# MikerBotBottlenose.net
KiCad netlist of a schematic drawn in EAGLE
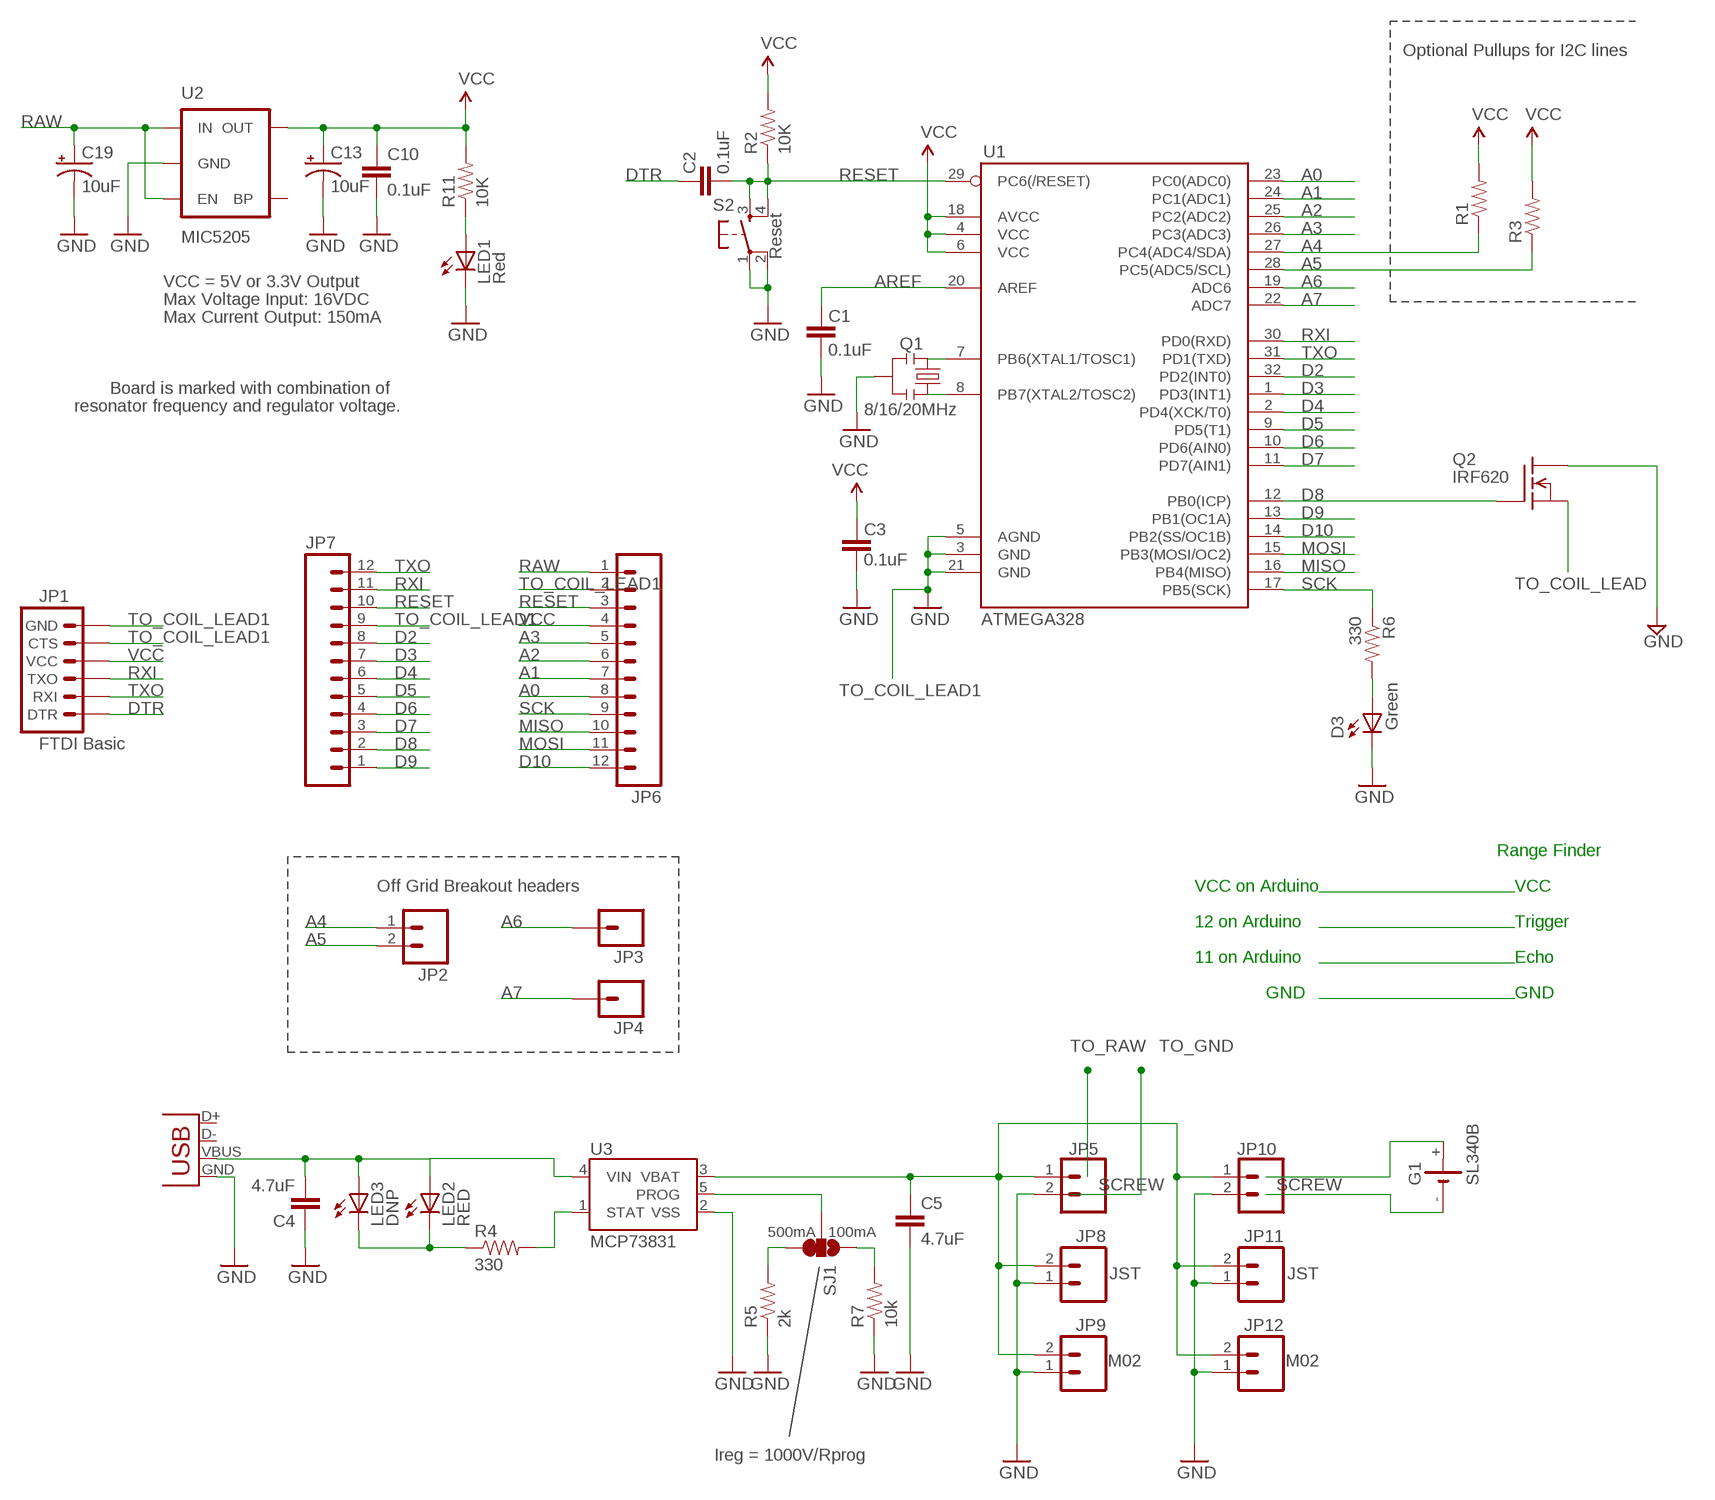
[diagram p0: schematic, sheet 1]

(export (version "E")
  (design (tool "Eeschema 10.0.6"))
  (components
    (comp (ref "C1")
      (value "0.1uF")
      (footprint "eagle-import:0402-CAP")
      (libsource (lib "eagle-import") (part "CAP0402-CAP"))
    )
    (comp (ref "C2")
      (value "0.1uF")
      (footprint "eagle-import:0402-CAP")
      (libsource (lib "eagle-import") (part "CAP0402-CAP"))
    )
    (comp (ref "C3")
      (value "0.1uF")
      (footprint "eagle-import:0402-CAP")
      (libsource (lib "eagle-import") (part "CAP0402-CAP"))
    )
    (comp (ref "C4")
      (value "4.7uF")
      (footprint "eagle-import:0402-CAP")
      (libsource (lib "eagle-import") (part "CAP0402-CAP"))
    )
    (comp (ref "C5")
      (value "4.7uF")
      (footprint "eagle-import:0402-CAP")
      (libsource (lib "eagle-import") (part "CAP0402-CAP"))
    )
    (comp (ref "C10")
      (value "0.1uF")
      (footprint "eagle-import:0402-CAP")
      (libsource (lib "eagle-import") (part "CAP0402-CAP"))
    )
    (comp (ref "C13")
      (value "10uF")
      (footprint "eagle-import:EIA3216")
      (libsource (lib "eagle-import") (part "CAP_POL1206"))
    )
    (comp (ref "C19")
      (value "10uF")
      (footprint "eagle-import:EIA3216")
      (libsource (lib "eagle-import") (part "CAP_POL1206"))
    )
    (comp (ref "D3")
      (value "Green")
      (footprint "eagle-import:LED-0603")
      (libsource (lib "eagle-import") (part "LED0603"))
    )
    (comp (ref "G1")
      (value "SL340B")
      (footprint "eagle-import:SL-340_B3.6V")
      (libsource (lib "eagle-import") (part "SL340B"))
    )
    (comp (ref "JP1")
      (value "FTDI Basic")
      (footprint "eagle-import:1X06")
      (libsource (lib "eagle-import") (part "ARDUINO_SERIAL_PROGRAMPTH"))
    )
    (comp (ref "JP2")
      (value "M02PTH")
      (footprint "eagle-import:1X02")
      (libsource (lib "eagle-import") (part "M02PTH"))
    )
    (comp (ref "JP3")
      (value "M01PTH")
      (footprint "eagle-import:1X01")
      (libsource (lib "eagle-import") (part "M01PTH"))
    )
    (comp (ref "JP4")
      (value "M01PTH")
      (footprint "eagle-import:1X01")
      (libsource (lib "eagle-import") (part "M01PTH"))
    )
    (comp (ref "JP5")
      (value "SCREW")
      (footprint "eagle-import:SCREWTERMINAL-3.5MM-2-NS")
      (libsource (lib "eagle-import") (part "M023.5MM-NO_SILK"))
    )
    (comp (ref "JP6")
      (value "M12PTH")
      (footprint "eagle-import:1X12")
      (libsource (lib "eagle-import") (part "M12PTH"))
    )
    (comp (ref "JP7")
      (value "M12PTH")
      (footprint "eagle-import:1X12")
      (libsource (lib "eagle-import") (part "M12PTH"))
    )
    (comp (ref "JP8")
      (value "JST")
      (footprint "eagle-import:JST-2-PTH")
      (libsource (lib "eagle-import") (part "M02JST-PTH-2"))
    )
    (comp (ref "JP9")
      (value "M02")
      (footprint "eagle-import:1X02")
      (libsource (lib "eagle-import") (part "M02PTH"))
    )
    (comp (ref "JP10")
      (value "SCREW")
      (footprint "eagle-import:SCREWTERMINAL-3.5MM-2-NS")
      (libsource (lib "eagle-import") (part "M023.5MM-NO_SILK"))
    )
    (comp (ref "JP11")
      (value "JST")
      (footprint "eagle-import:JST-2-PTH")
      (libsource (lib "eagle-import") (part "M02JST-PTH-2"))
    )
    (comp (ref "JP12")
      (value "M02")
      (footprint "eagle-import:1X02")
      (libsource (lib "eagle-import") (part "M02PTH"))
    )
    (comp (ref "LED1")
      (value "Red")
      (footprint "eagle-import:LED-0603")
      (libsource (lib "eagle-import") (part "LED0603"))
    )
    (comp (ref "LED2")
      (value "RED")
      (footprint "eagle-import:LED-0603")
      (libsource (lib "eagle-import") (part "LED0603"))
    )
    (comp (ref "LED3")
      (value "DNP")
      (footprint "eagle-import:LED3MM")
      (libsource (lib "eagle-import") (part "LED3MM"))
    )
    (comp (ref "Q1")
      (value "8/16/20MHz")
      (footprint "eagle-import:RESONATOR-SMD")
      (libsource (lib "eagle-import") (part "RESONATORSMD"))
    )
    (comp (ref "Q2")
      (value "IRF620")
      (footprint "eagle-import:TO220")
      (libsource (lib "eagle-import") (part "IRF620"))
    )
    (comp (ref "R1")
      (value "RESISTOR0402-RES")
      (footprint "eagle-import:0402-RES")
      (libsource (lib "eagle-import") (part "RESISTOR0402-RES"))
    )
    (comp (ref "R2")
      (value "10K")
      (footprint "eagle-import:0402-RES")
      (libsource (lib "eagle-import") (part "RESISTOR0402-RES"))
    )
    (comp (ref "R3")
      (value "RESISTOR0402-RES")
      (footprint "eagle-import:0402-RES")
      (libsource (lib "eagle-import") (part "RESISTOR0402-RES"))
    )
    (comp (ref "R4")
      (value "330")
      (footprint "eagle-import:0402-RES")
      (libsource (lib "eagle-import") (part "RESISTOR0402-RES"))
    )
    (comp (ref "R5")
      (value "2k")
      (footprint "eagle-import:0402-RES")
      (libsource (lib "eagle-import") (part "RESISTOR0402-RES"))
    )
    (comp (ref "R6")
      (value "330")
      (footprint "eagle-import:0402-RES")
      (libsource (lib "eagle-import") (part "RESISTOR0402-RES"))
    )
    (comp (ref "R7")
      (value "10k")
      (footprint "eagle-import:0402-RES")
      (libsource (lib "eagle-import") (part "RESISTOR0402-RES"))
    )
    (comp (ref "R11")
      (value "10K")
      (footprint "eagle-import:0402-RES")
      (libsource (lib "eagle-import") (part "RESISTOR0402-RES"))
    )
    (comp (ref "S2")
      (value "Reset")
      (footprint "eagle-import:TACTILE_SWITCH_SMD")
      (libsource (lib "eagle-import") (part "TAC_SWITCHSMD"))
    )
    (comp (ref "SJ1")
      (value "SOLDERJUMPER_2WAYS")
      (footprint "eagle-import:SJ_3")
      (libsource (lib "eagle-import") (part "SOLDERJUMPER_2WAYS"))
    )
    (comp (ref "U1")
      (value "ATMEGA328")
      (footprint "eagle-import:TQFP32-08")
      (libsource (lib "eagle-import") (part "ATMEGA168"))
    )
    (comp (ref "U2")
      (value "MIC5205")
      (footprint "eagle-import:SOT23-5")
      (libsource (lib "eagle-import") (part "V_REG_LDOSMD"))
    )
    (comp (ref "U3")
      (value "MCP73831")
      (footprint "eagle-import:SOT23-5")
      (libsource (lib "eagle-import") (part "MCP73831"))
    )
    (comp (ref "X1")
      (value "USBSMD")
      (footprint "eagle-import:USB-MINIB")
      (libsource (lib "eagle-import") (part "USBSMD"))
    )
  )
  (nets
    (net (code "1") (name "/A0") (class "Default")
      (node (ref "JP6") (pin "8") (pinfunction "8_8") (pintype "passive"))
      (node (ref "U1") (pin "23") (pinfunction "PC0(ADC0)_23") (pintype "bidirectional"))
    )
    (net (code "2") (name "/A1") (class "Default")
      (node (ref "JP6") (pin "7") (pinfunction "7_7") (pintype "passive"))
      (node (ref "U1") (pin "24") (pinfunction "PC1(ADC1)_24") (pintype "bidirectional"))
    )
    (net (code "3") (name "/A2") (class "Default")
      (node (ref "JP6") (pin "6") (pinfunction "6_6") (pintype "passive"))
      (node (ref "U1") (pin "25") (pinfunction "PC2(ADC2)_25") (pintype "bidirectional"))
    )
    (net (code "4") (name "/A3") (class "Default")
      (node (ref "JP6") (pin "5") (pinfunction "5_5") (pintype "passive"))
      (node (ref "U1") (pin "26") (pinfunction "PC3(ADC3)_26") (pintype "bidirectional"))
    )
    (net (code "5") (name "/A4") (class "Default")
      (node (ref "JP2") (pin "1") (pinfunction "1_1") (pintype "passive"))
      (node (ref "R1") (pin "1") (pinfunction "1_1") (pintype "passive"))
      (node (ref "U1") (pin "27") (pinfunction "PC4(ADC4/SDA)_27") (pintype "bidirectional"))
    )
    (net (code "6") (name "/A5") (class "Default")
      (node (ref "JP2") (pin "2") (pinfunction "2_2") (pintype "passive"))
      (node (ref "R3") (pin "1") (pinfunction "1_1") (pintype "passive"))
      (node (ref "U1") (pin "28") (pinfunction "PC5(ADC5/SCL)_28") (pintype "bidirectional"))
    )
    (net (code "7") (name "/A6") (class "Default")
      (node (ref "JP3") (pin "1") (pinfunction "1_1") (pintype "passive"))
      (node (ref "U1") (pin "19") (pinfunction "ADC6_19") (pintype "bidirectional"))
    )
    (net (code "8") (name "/A7") (class "Default")
      (node (ref "JP4") (pin "1") (pinfunction "1_1") (pintype "passive"))
      (node (ref "U1") (pin "22") (pinfunction "ADC7_22") (pintype "bidirectional"))
    )
    (net (code "9") (name "/AREF") (class "Default")
      (node (ref "C1") (pin "2") (pinfunction "2_2") (pintype "passive"))
      (node (ref "U1") (pin "20") (pinfunction "AREF_20") (pintype "bidirectional"))
    )
    (net (code "10") (name "/D2") (class "Default")
      (node (ref "JP7") (pin "8") (pinfunction "8_8") (pintype "passive"))
      (node (ref "U1") (pin "32") (pinfunction "PD2(INT0)_32") (pintype "bidirectional"))
    )
    (net (code "11") (name "/D3") (class "Default")
      (node (ref "JP7") (pin "7") (pinfunction "7_7") (pintype "passive"))
      (node (ref "U1") (pin "1") (pinfunction "PD3(INT1)_1") (pintype "bidirectional"))
    )
    (net (code "12") (name "/D4") (class "Default")
      (node (ref "JP7") (pin "6") (pinfunction "6_6") (pintype "passive"))
      (node (ref "U1") (pin "2") (pinfunction "PD4(XCK/T0)_2") (pintype "bidirectional"))
    )
    (net (code "13") (name "/D5") (class "Default")
      (node (ref "JP7") (pin "5") (pinfunction "5_5") (pintype "passive"))
      (node (ref "U1") (pin "9") (pinfunction "PD5(T1)_9") (pintype "bidirectional"))
    )
    (net (code "14") (name "/D6") (class "Default")
      (node (ref "JP7") (pin "4") (pinfunction "4_4") (pintype "passive"))
      (node (ref "U1") (pin "10") (pinfunction "PD6(AIN0)_10") (pintype "bidirectional"))
    )
    (net (code "15") (name "/D7") (class "Default")
      (node (ref "JP7") (pin "3") (pinfunction "3_3") (pintype "passive"))
      (node (ref "U1") (pin "11") (pinfunction "PD7(AIN1)_11") (pintype "bidirectional"))
    )
    (net (code "16") (name "/D8") (class "Default")
      (node (ref "JP7") (pin "2") (pinfunction "2_2") (pintype "passive"))
      (node (ref "Q2") (pin "1") (pinfunction "G_1") (pintype "passive"))
      (node (ref "U1") (pin "12") (pinfunction "PB0(ICP)_12") (pintype "bidirectional"))
    )
    (net (code "17") (name "/D9") (class "Default")
      (node (ref "JP7") (pin "1") (pinfunction "1_1") (pintype "passive"))
      (node (ref "U1") (pin "13") (pinfunction "PB1(OC1A)_13") (pintype "bidirectional"))
    )
    (net (code "18") (name "/D10") (class "Default")
      (node (ref "JP6") (pin "12") (pinfunction "12_12") (pintype "passive"))
      (node (ref "U1") (pin "14") (pinfunction "PB2(SS/OC1B)_14") (pintype "bidirectional"))
    )
    (net (code "19") (name "/DTR") (class "Default")
      (node (ref "C2") (pin "2") (pinfunction "2_2") (pintype "passive"))
      (node (ref "JP1") (pin "1") (pinfunction "DTR_1") (pintype "passive"))
    )
    (net (code "20") (name "/MISO") (class "Default")
      (node (ref "JP6") (pin "10") (pinfunction "10_10") (pintype "passive"))
      (node (ref "U1") (pin "16") (pinfunction "PB4(MISO)_16") (pintype "bidirectional"))
    )
    (net (code "21") (name "/MOSI") (class "Default")
      (node (ref "JP6") (pin "11") (pinfunction "11_11") (pintype "passive"))
      (node (ref "U1") (pin "15") (pinfunction "PB3(MOSI/OC2)_15") (pintype "bidirectional"))
    )
    (net (code "22") (name "/RAW") (class "Default")
      (node (ref "C19") (pin "A") (pinfunction "+_A") (pintype "passive"))
      (node (ref "JP6") (pin "1") (pinfunction "1_1") (pintype "passive"))
      (node (ref "U2") (pin "1") (pinfunction "IN_1") (pintype "input"))
      (node (ref "U2") (pin "3") (pinfunction "EN_3") (pintype "input"))
    )
    (net (code "23") (name "/RESET") (class "Default")
      (node (ref "C2") (pin "1") (pinfunction "1_1") (pintype "passive"))
      (node (ref "JP6") (pin "3") (pinfunction "3_3") (pintype "passive"))
      (node (ref "JP7") (pin "10") (pinfunction "10_10") (pintype "passive"))
      (node (ref "R2") (pin "1") (pinfunction "1_1") (pintype "passive"))
      (node (ref "S2") (pin "3") (pinfunction "3_3") (pintype "passive"))
      (node (ref "S2") (pin "4") (pinfunction "4_4") (pintype "passive"))
      (node (ref "U1") (pin "29") (pinfunction "PC6(/RESET)_29") (pintype "bidirectional"))
    )
    (net (code "24") (name "/RXI") (class "Default")
      (node (ref "JP1") (pin "3") (pinfunction "TXO_3") (pintype "passive"))
      (node (ref "JP7") (pin "11") (pinfunction "11_11") (pintype "passive"))
      (node (ref "U1") (pin "30") (pinfunction "PD0(RXD)_30") (pintype "bidirectional"))
    )
    (net (code "25") (name "/SCK") (class "Default")
      (node (ref "JP6") (pin "9") (pinfunction "9_9") (pintype "passive"))
      (node (ref "R6") (pin "1") (pinfunction "1_1") (pintype "passive"))
      (node (ref "U1") (pin "17") (pinfunction "PB5(SCK)_17") (pintype "bidirectional"))
    )
    (net (code "26") (name "/TO_COIL_LEAD") (class "Default")
      (node (ref "Q2") (pin "3") (pinfunction "S_3") (pintype "passive"))
    )
    (net (code "29") (name "/TXO") (class "Default")
      (node (ref "JP1") (pin "2") (pinfunction "RXI_2") (pintype "passive"))
      (node (ref "JP7") (pin "12") (pinfunction "12_12") (pintype "passive"))
      (node (ref "U1") (pin "31") (pinfunction "PD1(TXD)_31") (pintype "bidirectional"))
    )
    (net (code "30") (name "GND") (class "Default")
      (node (ref "C1") (pin "1") (pinfunction "1_1") (pintype "passive"))
      (node (ref "C10") (pin "2") (pinfunction "2_2") (pintype "passive"))
      (node (ref "C13") (pin "C") (pinfunction "-_C") (pintype "passive"))
      (node (ref "C19") (pin "C") (pinfunction "-_C") (pintype "passive"))
      (node (ref "C3") (pin "1") (pinfunction "1_1") (pintype "passive"))
      (node (ref "C4") (pin "1") (pinfunction "1_1") (pintype "passive"))
      (node (ref "C5") (pin "2") (pinfunction "2_2") (pintype "passive"))
      (node (ref "D3") (pin "C") (pinfunction "C_C") (pintype "passive"))
      (node (ref "JP1") (pin "5") (pinfunction "CTS_5") (pintype "passive"))
      (node (ref "JP1") (pin "6") (pinfunction "GND_6") (pintype "passive"))
      (node (ref "JP10") (pin "2") (pinfunction "2_2") (pintype "passive"))
      (node (ref "JP11") (pin "1") (pinfunction "1_1") (pintype "passive"))
      (node (ref "JP12") (pin "1") (pinfunction "1_1") (pintype "passive"))
      (node (ref "JP5") (pin "2") (pinfunction "2_2") (pintype "passive"))
      (node (ref "JP6") (pin "2") (pinfunction "2_2") (pintype "passive"))
      (node (ref "JP7") (pin "9") (pinfunction "9_9") (pintype "passive"))
      (node (ref "JP8") (pin "1") (pinfunction "1_1") (pintype "passive"))
      (node (ref "JP9") (pin "1") (pinfunction "1_1") (pintype "passive"))
      (node (ref "LED1") (pin "C") (pinfunction "C_C") (pintype "passive"))
      (node (ref "Q1") (pin "2") (pinfunction "2_2") (pintype "passive"))
      (node (ref "Q2") (pin "2") (pinfunction "D_2") (pintype "passive"))
      (node (ref "R5") (pin "1") (pinfunction "1_1") (pintype "passive"))
      (node (ref "R7") (pin "1") (pinfunction "1_1") (pintype "passive"))
      (node (ref "S2") (pin "1") (pinfunction "1_1") (pintype "passive"))
      (node (ref "S2") (pin "2") (pinfunction "2_2") (pintype "passive"))
      (node (ref "U1") (pin "21") (pinfunction "GND_21") (pintype "bidirectional"))
      (node (ref "U1") (pin "3") (pinfunction "GND_3") (pintype "bidirectional"))
      (node (ref "U1") (pin "5") (pinfunction "AGND_5") (pintype "bidirectional"))
      (node (ref "U2") (pin "2") (pinfunction "GND_2") (pintype "input"))
      (node (ref "U3") (pin "2") (pinfunction "VSS_2") (pintype "power_in"))
      (node (ref "X1") (pin "GND") (pinfunction "GND_GND") (pintype "bidirectional"))
    )
    (net (code "31") (name "Net-(D3-PadA)") (class "Default")
      (node (ref "D3") (pin "A") (pinfunction "A_A") (pintype "passive"))
      (node (ref "R6") (pin "2") (pinfunction "2_2") (pintype "passive"))
    )
    (net (code "32") (name "Net-(LED1-PadA)") (class "Default")
      (node (ref "LED1") (pin "A") (pinfunction "A_A") (pintype "passive"))
      (node (ref "R11") (pin "1") (pinfunction "1_1") (pintype "passive"))
    )
    (net (code "33") (name "Net-(LED3-C)") (class "Default")
      (node (ref "LED2") (pin "C") (pinfunction "C_C") (pintype "passive"))
      (node (ref "LED3") (pin "K") (pinfunction "C_K") (pintype "passive"))
      (node (ref "R4") (pin "1") (pinfunction "1_1") (pintype "passive"))
    )
    (net (code "34") (name "Net-(R5-Pad2)") (class "Default")
      (node (ref "R5") (pin "2") (pinfunction "2_2") (pintype "passive"))
      (node (ref "SJ1") (pin "3") (pinfunction "3_3") (pintype "passive"))
    )
    (net (code "35") (name "Net-(R7-Pad2)") (class "Default")
      (node (ref "R7") (pin "2") (pinfunction "2_2") (pintype "passive"))
      (node (ref "SJ1") (pin "1") (pinfunction "1_1") (pintype "passive"))
    )
    (net (code "36") (name "Net-(U1-PB6(XTAL1{slash}TOSC1))") (class "Default")
      (node (ref "Q1") (pin "3") (pinfunction "3_3") (pintype "passive"))
      (node (ref "U1") (pin "7") (pinfunction "PB6(XTAL1/TOSC1)_7") (pintype "bidirectional"))
    )
    (net (code "37") (name "Net-(U1-PB7(XTAL2{slash}TOSC2))") (class "Default")
      (node (ref "Q1") (pin "1") (pinfunction "1_1") (pintype "passive"))
      (node (ref "U1") (pin "8") (pinfunction "PB7(XTAL2/TOSC2)_8") (pintype "bidirectional"))
    )
    (net (code "38") (name "Net-(U3-PROG)") (class "Default")
      (node (ref "SJ1") (pin "2") (pinfunction "2_2") (pintype "passive"))
      (node (ref "U3") (pin "5") (pinfunction "PROG_5") (pintype "input"))
    )
    (net (code "39") (name "Net-(U3-STAT)") (class "Default")
      (node (ref "R4") (pin "2") (pinfunction "2_2") (pintype "passive"))
      (node (ref "U3") (pin "1") (pinfunction "STAT_1") (pintype "output"))
    )
    (net (code "40") (name "Net-(U3-VBAT)") (class "Default")
      (node (ref "C5") (pin "1") (pinfunction "1_1") (pintype "passive"))
      (node (ref "JP10") (pin "1") (pinfunction "1_1") (pintype "passive"))
      (node (ref "JP11") (pin "2") (pinfunction "2_2") (pintype "passive"))
      (node (ref "JP12") (pin "2") (pinfunction "2_2") (pintype "passive"))
      (node (ref "JP5") (pin "1") (pinfunction "1_1") (pintype "passive"))
      (node (ref "JP8") (pin "2") (pinfunction "2_2") (pintype "passive"))
      (node (ref "JP9") (pin "2") (pinfunction "2_2") (pintype "passive"))
      (node (ref "U3") (pin "3") (pinfunction "VBAT_3") (pintype "power_in"))
    )
    (net (code "41") (name "Net-(U3-VIN)") (class "Default")
      (node (ref "C4") (pin "2") (pinfunction "2_2") (pintype "passive"))
      (node (ref "LED2") (pin "A") (pinfunction "A_A") (pintype "passive"))
      (node (ref "LED3") (pin "A") (pinfunction "A_A") (pintype "passive"))
      (node (ref "U3") (pin "4") (pinfunction "VIN_4") (pintype "power_in"))
      (node (ref "X1") (pin "VBUS") (pinfunction "VBUS_VBUS") (pintype "bidirectional"))
    )
    (net (code "42") (name "VCC") (class "Default")
      (node (ref "C10") (pin "1") (pinfunction "1_1") (pintype "passive"))
      (node (ref "C13") (pin "A") (pinfunction "+_A") (pintype "passive"))
      (node (ref "C3") (pin "2") (pinfunction "2_2") (pintype "passive"))
      (node (ref "JP1") (pin "4") (pinfunction "VCC_4") (pintype "passive"))
      (node (ref "JP6") (pin "4") (pinfunction "4_4") (pintype "passive"))
      (node (ref "R1") (pin "2") (pinfunction "2_2") (pintype "passive"))
      (node (ref "R11") (pin "2") (pinfunction "2_2") (pintype "passive"))
      (node (ref "R2") (pin "2") (pinfunction "2_2") (pintype "passive"))
      (node (ref "R3") (pin "2") (pinfunction "2_2") (pintype "passive"))
      (node (ref "U1") (pin "18") (pinfunction "AVCC_18") (pintype "bidirectional"))
      (node (ref "U1") (pin "4") (pinfunction "VCC_4") (pintype "bidirectional"))
      (node (ref "U1") (pin "6") (pinfunction "VCC_6") (pintype "bidirectional"))
      (node (ref "U2") (pin "5") (pinfunction "OUT_5") (pintype "passive"))
    )
    (net (code "43") (name "unconnected-(G1-Pad+)") (class "Default")
      (node (ref "G1") (pin "+") (pinfunction "+_+") (pintype "passive"))
    )
    (net (code "44") (name "unconnected-(G1-Pad-)") (class "Default")
      (node (ref "G1") (pin "-") (pinfunction "-_-") (pintype "passive"))
    )
    (net (code "45") (name "unconnected-(U2-BP-Pad4)") (class "Default")
      (node (ref "U2") (pin "4") (pinfunction "BP_4") (pintype "input"))
    )
    (net (code "46") (name "unconnected-(X1-PadD+)") (class "Default")
      (node (ref "X1") (pin "D+") (pinfunction "D+_D+") (pintype "bidirectional"))
    )
    (net (code "47") (name "unconnected-(X1-PadD-)") (class "Default")
      (node (ref "X1") (pin "D-") (pinfunction "D-_D-") (pintype "bidirectional"))
    )
  )
)
